# Radiator.net
KiCad netlist of a schematic drawn in Altium Designer
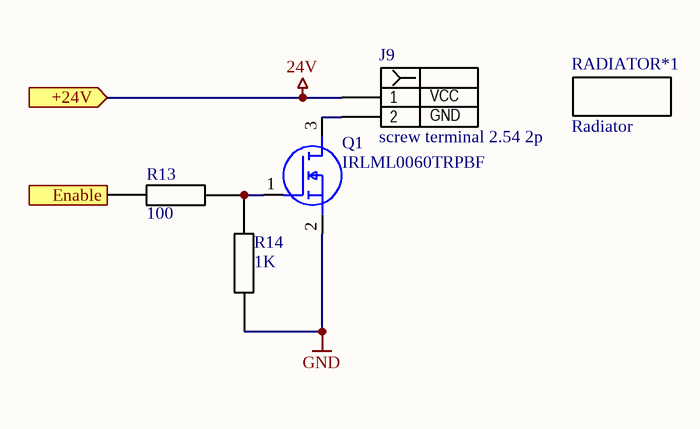
[diagram p0: Radiator.SchDoc]

(export (version "E")
  (design (tool "Eeschema 10.0.6"))
  (components
    (comp (ref "J9")
      (value "screw terminal 2.54 2p")
      (footprint "1725672-2-2.54")
      (description "Connector")
      (fields
        (field (name "MANUFACTURER_PART_NUMBER") "1725672")
        (field (name "MOUSER PART NUMBER") "651-1725672")
      )
      (libsource (lib "RobotLib") (part "screw terminal 2.54 2p"))
    )
    (comp (ref "Q1")
      (value "IRLML0060TRPBF")
      (footprint "SamacSys:SOT95P237X112-3N")
      (description "MOSFET (N-Channel)")
      (fields (field (name "MOUSER PART NUMBER") "942-IRLML0060TRPBF"))
      (libsource (lib "*") (part "IRLML0060TRPBF"))
    )
    (comp (ref "R13")
      (value "100")
      (footprint "SamacSys:RESC1608X55N")
      (description "100 0603")
      (fields
        (field (name "MANUFACTURER_PART_NUMBER") "CPF0603B100RE1")
        (field (name "MOUSER PART NUMBER") "279-CPF0603B100RE1")
      )
      (libsource (lib "RobotLib") (part "res 0603"))
    )
    (comp (ref "R14")
      (value "1K")
      (footprint "SamacSys:RESC1608X55N")
      (description "1k 0603")
      (fields
        (field (name "MANUFACTURER_PART_NUMBER") "CPF0603B100RE1")
        (field (name "MOUSER PART NUMBER") "279-CPF0603B100RE1")
      )
      (libsource (lib "") (part "res 0603_1"))
    )
    (comp (ref "RADIATOR*1")
      (value "Radiator")
      (footprint "SK68-75-SA")
      (libsource (lib "RobotLib") (part "Radiator"))
    )
  )
  (nets
    (net (code "1") (name "/Enable") (class "Default")
      (node (ref "R13") (pin "2") (pinfunction "2_2") (pintype "passive"))
    )
    (net (code "2") (name "24V") (class "Default")
      (node (ref "J9") (pin "1") (pinfunction "1_1") (pintype "passive"))
    )
    (net (code "3") (name "GND") (class "Default")
      (node (ref "Q1") (pin "2") (pinfunction "S_2") (pintype "passive"))
      (node (ref "R14") (pin "1") (pinfunction "1_1") (pintype "passive"))
    )
    (net (code "4") (name "Net-(Q1-D)") (class "Default")
      (node (ref "J9") (pin "2") (pinfunction "2_2") (pintype "passive"))
      (node (ref "Q1") (pin "3") (pinfunction "D_3") (pintype "passive"))
    )
    (net (code "5") (name "Net-(Q1-G)") (class "Default")
      (node (ref "Q1") (pin "1") (pinfunction "G_1") (pintype "passive"))
      (node (ref "R13") (pin "1") (pinfunction "1_1") (pintype "passive"))
      (node (ref "R14") (pin "2") (pinfunction "2_2") (pintype "passive"))
    )
  )
)
